# led.net
KiCad netlist of a schematic drawn in Altium Designer
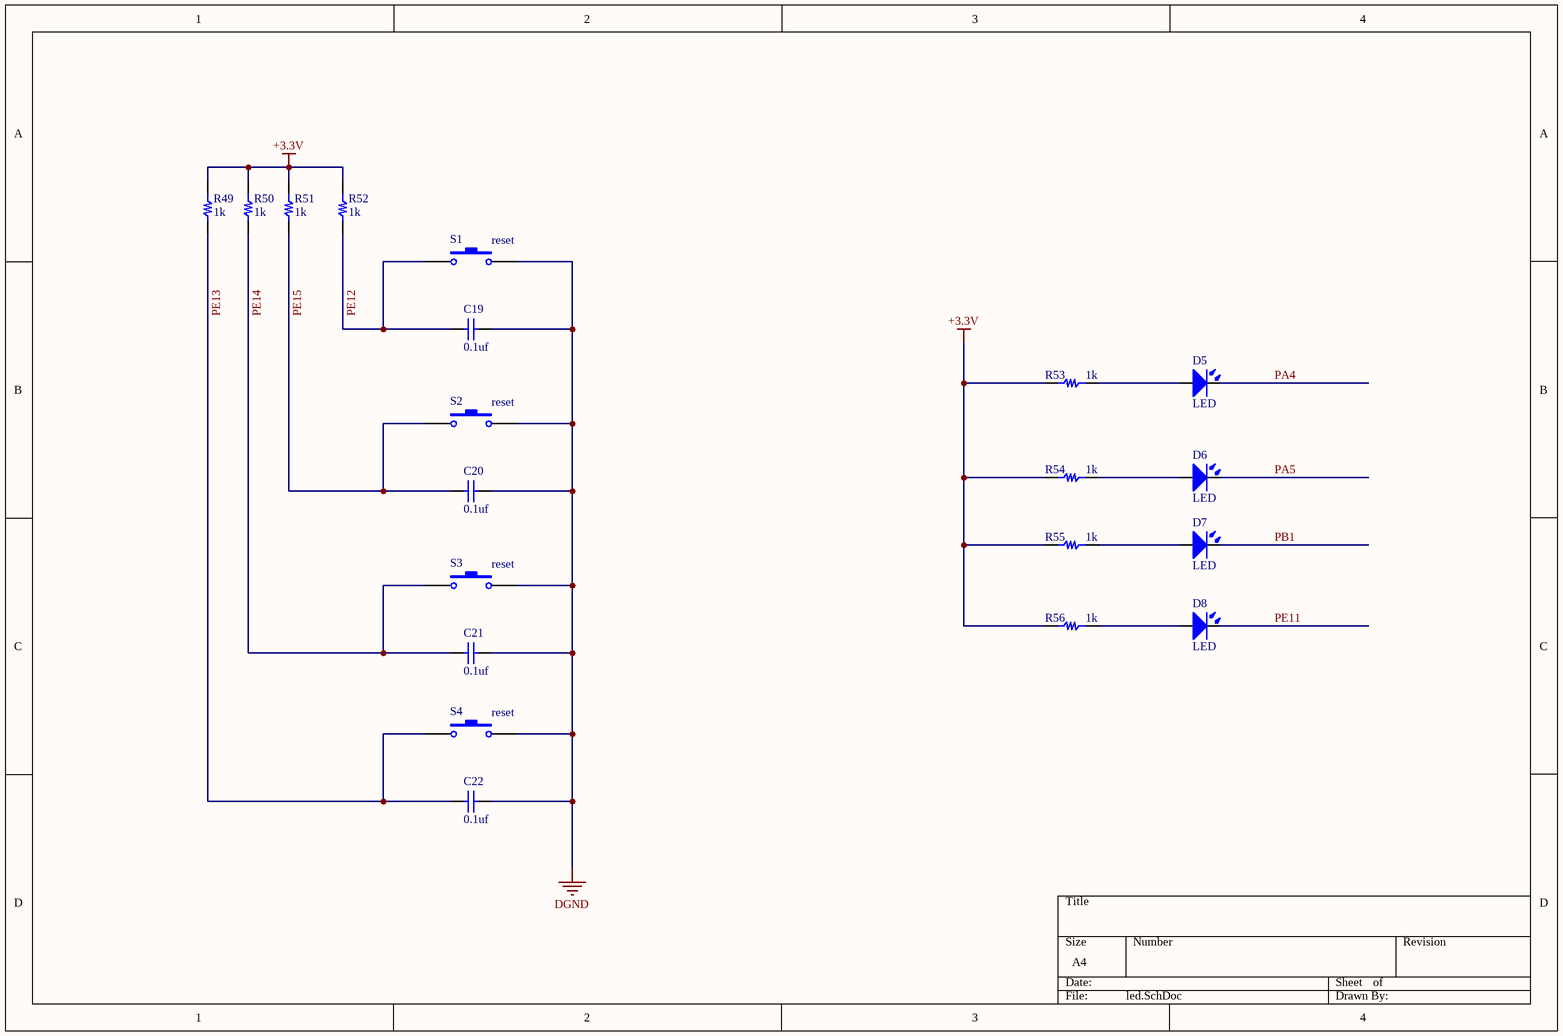
[diagram p0: led.SchDoc]

(export (version "E")
  (design (tool "Eeschema 10.0.6"))
  (components
    (comp (ref "C19")
      (value "0.1uf")
      (footprint "0805C")
      (description "贴片电容")
      (fields (field (name "PUBLISHER") "Altium Limited"))
      (libsource (lib "Device_CHT") (part "Cap"))
    )
    (comp (ref "C20")
      (value "0.1uf")
      (footprint "0805C")
      (description "贴片电容")
      (fields (field (name "PUBLISHER") "Altium Limited"))
      (libsource (lib "Device_CHT") (part "Cap"))
    )
    (comp (ref "C21")
      (value "0.1uf")
      (footprint "0805C")
      (description "贴片电容")
      (fields (field (name "PUBLISHER") "Altium Limited"))
      (libsource (lib "Device_CHT") (part "Cap"))
    )
    (comp (ref "C22")
      (value "0.1uf")
      (footprint "0805C")
      (description "贴片电容")
      (fields (field (name "PUBLISHER") "Altium Limited"))
      (libsource (lib "Device_CHT") (part "Cap"))
    )
    (comp (ref "D5")
      (value "LED")
      (footprint "0805-LED-RED")
      (description "Typical INFRARED GaAs LED")
      (fields (field (name "PUBLISHER") "Altium Limited"))
      (libsource (lib "Device_CHT") (part "LED"))
    )
    (comp (ref "D6")
      (value "LED")
      (footprint "0805-LED-RED")
      (description "Typical INFRARED GaAs LED")
      (fields (field (name "PUBLISHER") "Altium Limited"))
      (libsource (lib "Device_CHT") (part "LED"))
    )
    (comp (ref "D7")
      (value "LED")
      (footprint "0805-LED-RED")
      (description "Typical INFRARED GaAs LED")
      (fields (field (name "PUBLISHER") "Altium Limited"))
      (libsource (lib "Device_CHT") (part "LED"))
    )
    (comp (ref "D8")
      (value "LED")
      (footprint "0805-LED-RED")
      (description "Typical INFRARED GaAs LED")
      (fields (field (name "PUBLISHER") "Altium Limited"))
      (libsource (lib "Device_CHT") (part "LED"))
    )
    (comp (ref "R49")
      (value "1k")
      (footprint "0805_small")
      (description "电阻")
      (fields (field (name "PUBLISHER") "Altium Limited"))
      (libsource (lib "Device_CHT") (part "Res"))
    )
    (comp (ref "R50")
      (value "1k")
      (footprint "0805_small")
      (description "电阻")
      (fields (field (name "PUBLISHER") "Altium Limited"))
      (libsource (lib "Device_CHT") (part "Res"))
    )
    (comp (ref "R51")
      (value "1k")
      (footprint "0805_small")
      (description "电阻")
      (fields (field (name "PUBLISHER") "Altium Limited"))
      (libsource (lib "Device_CHT") (part "Res"))
    )
    (comp (ref "R52")
      (value "1k")
      (footprint "0805_small")
      (description "电阻")
      (fields (field (name "PUBLISHER") "Altium Limited"))
      (libsource (lib "Device_CHT") (part "Res"))
    )
    (comp (ref "R53")
      (value "1k")
      (footprint "0805_small")
      (description "电阻")
      (fields (field (name "PUBLISHER") "Altium Limited"))
      (libsource (lib "Device_CHT") (part "Res"))
    )
    (comp (ref "R54")
      (value "1k")
      (footprint "0805_small")
      (description "电阻")
      (fields (field (name "PUBLISHER") "Altium Limited"))
      (libsource (lib "Device_CHT") (part "Res"))
    )
    (comp (ref "R55")
      (value "1k")
      (footprint "0805_small")
      (description "电阻")
      (fields (field (name "PUBLISHER") "Altium Limited"))
      (libsource (lib "Device_CHT") (part "Res"))
    )
    (comp (ref "R56")
      (value "1k")
      (footprint "0805_small")
      (description "电阻")
      (fields (field (name "PUBLISHER") "Altium Limited"))
      (libsource (lib "Device_CHT") (part "Res"))
    )
    (comp (ref "S1")
      (value "reset")
      (footprint "k_TS_021")
      (description "Switch")
      (fields (field (name "PUBLISHER") "Altium Limited"))
      (libsource (lib "Device_CHT") (part "SW-PB-2"))
    )
    (comp (ref "S2")
      (value "reset")
      (footprint "k_TS_021")
      (description "Switch")
      (fields (field (name "PUBLISHER") "Altium Limited"))
      (libsource (lib "Device_CHT") (part "SW-PB-2"))
    )
    (comp (ref "S3")
      (value "reset")
      (footprint "k_TS_021")
      (description "Switch")
      (fields (field (name "PUBLISHER") "Altium Limited"))
      (libsource (lib "Device_CHT") (part "SW-PB-2"))
    )
    (comp (ref "S4")
      (value "reset")
      (footprint "k_TS_021")
      (description "Switch")
      (fields (field (name "PUBLISHER") "Altium Limited"))
      (libsource (lib "Device_CHT") (part "SW-PB-2"))
    )
  )
  (nets
    (net (code "1") (name "+3.3V") (class "Default")
      (node (ref "R49") (pin "1") (pinfunction "1_1") (pintype "passive"))
      (node (ref "R50") (pin "1") (pinfunction "1_1") (pintype "passive"))
      (node (ref "R51") (pin "1") (pinfunction "1_1") (pintype "passive"))
      (node (ref "R52") (pin "1") (pinfunction "1_1") (pintype "passive"))
      (node (ref "R53") (pin "2") (pinfunction "2_2") (pintype "passive"))
      (node (ref "R54") (pin "2") (pinfunction "2_2") (pintype "passive"))
      (node (ref "R55") (pin "2") (pinfunction "2_2") (pintype "passive"))
      (node (ref "R56") (pin "2") (pinfunction "2_2") (pintype "passive"))
    )
    (net (code "2") (name "/PA4") (class "Default")
      (node (ref "D5") (pin "2") (pinfunction "K_2") (pintype "passive"))
    )
    (net (code "3") (name "/PA5") (class "Default")
      (node (ref "D6") (pin "2") (pinfunction "K_2") (pintype "passive"))
    )
    (net (code "4") (name "/PB1") (class "Default")
      (node (ref "D7") (pin "2") (pinfunction "K_2") (pintype "passive"))
    )
    (net (code "5") (name "/PE11") (class "Default")
      (node (ref "D8") (pin "2") (pinfunction "K_2") (pintype "passive"))
    )
    (net (code "6") (name "/PE12") (class "Default")
      (node (ref "C19") (pin "2") (pinfunction "2_2") (pintype "passive"))
      (node (ref "R52") (pin "2") (pinfunction "2_2") (pintype "passive"))
      (node (ref "S1") (pin "1") (pinfunction "1_1") (pintype "passive"))
    )
    (net (code "7") (name "/PE13") (class "Default")
      (node (ref "C22") (pin "2") (pinfunction "2_2") (pintype "passive"))
      (node (ref "R49") (pin "2") (pinfunction "2_2") (pintype "passive"))
      (node (ref "S4") (pin "1") (pinfunction "1_1") (pintype "passive"))
    )
    (net (code "8") (name "/PE14") (class "Default")
      (node (ref "C21") (pin "2") (pinfunction "2_2") (pintype "passive"))
      (node (ref "R50") (pin "2") (pinfunction "2_2") (pintype "passive"))
      (node (ref "S3") (pin "1") (pinfunction "1_1") (pintype "passive"))
    )
    (net (code "9") (name "/PE15") (class "Default")
      (node (ref "C20") (pin "2") (pinfunction "2_2") (pintype "passive"))
      (node (ref "R51") (pin "2") (pinfunction "2_2") (pintype "passive"))
      (node (ref "S2") (pin "1") (pinfunction "1_1") (pintype "passive"))
    )
    (net (code "10") (name "DGND") (class "Default")
      (node (ref "C19") (pin "1") (pinfunction "1_1") (pintype "passive"))
      (node (ref "C20") (pin "1") (pinfunction "1_1") (pintype "passive"))
      (node (ref "C21") (pin "1") (pinfunction "1_1") (pintype "passive"))
      (node (ref "C22") (pin "1") (pinfunction "1_1") (pintype "passive"))
      (node (ref "S1") (pin "2") (pinfunction "2_2") (pintype "passive"))
      (node (ref "S2") (pin "2") (pinfunction "2_2") (pintype "passive"))
      (node (ref "S3") (pin "2") (pinfunction "2_2") (pintype "passive"))
      (node (ref "S4") (pin "2") (pinfunction "2_2") (pintype "passive"))
    )
    (net (code "11") (name "Net-(D5-A)") (class "Default")
      (node (ref "D5") (pin "1") (pinfunction "A_1") (pintype "passive"))
      (node (ref "R53") (pin "1") (pinfunction "1_1") (pintype "passive"))
    )
    (net (code "12") (name "Net-(D6-A)") (class "Default")
      (node (ref "D6") (pin "1") (pinfunction "A_1") (pintype "passive"))
      (node (ref "R54") (pin "1") (pinfunction "1_1") (pintype "passive"))
    )
    (net (code "13") (name "Net-(D7-A)") (class "Default")
      (node (ref "D7") (pin "1") (pinfunction "A_1") (pintype "passive"))
      (node (ref "R55") (pin "1") (pinfunction "1_1") (pintype "passive"))
    )
    (net (code "14") (name "Net-(D8-A)") (class "Default")
      (node (ref "D8") (pin "1") (pinfunction "A_1") (pintype "passive"))
      (node (ref "R56") (pin "1") (pinfunction "1_1") (pintype "passive"))
    )
  )
)
